# MDrive.net
KiCad netlist of a schematic drawn in Altium Designer
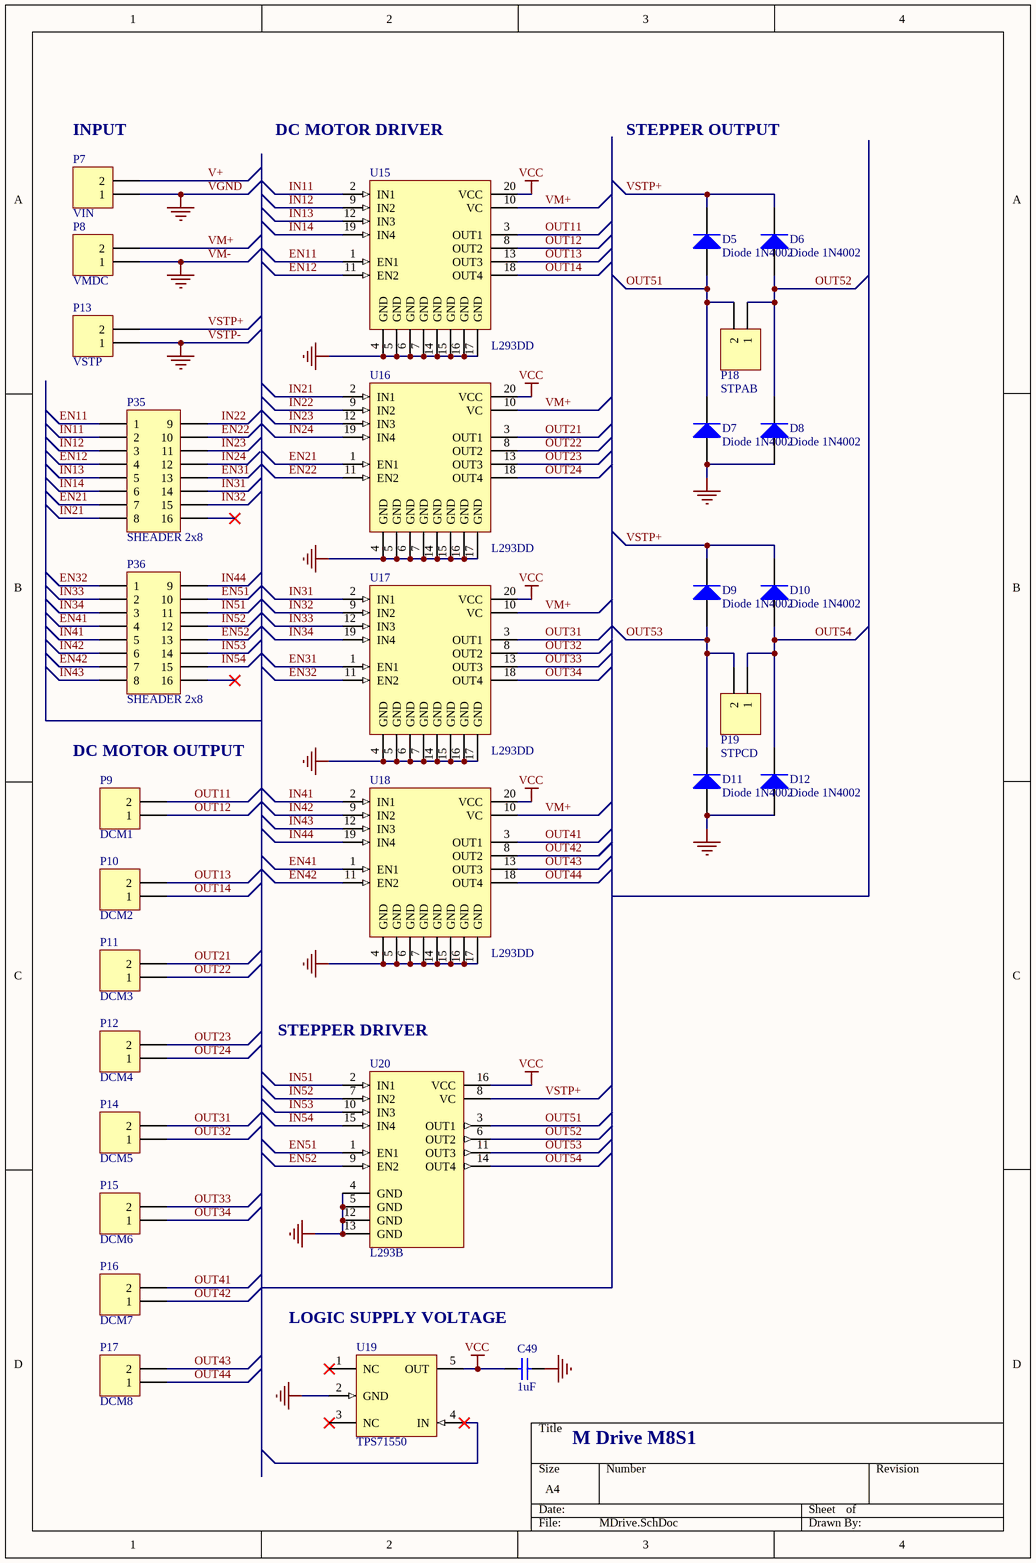
[diagram p0: MDrive.SchDoc]

(export (version "E")
  (design (tool "Eeschema 10.0.6"))
  (components
    (comp (ref "C49")
      (value "1uF")
      (footprint "CAPC2012M")
      (description "Capacitor (Semiconductor SIM Model)")
      (fields (field (name "Comment") "Cap Semi") (field (name "PUBLISHER") "Altium Limited"))
      (libsource (lib "Miscellaneous Devices") (part "Cap Semi"))
    )
    (comp (ref "D5")
      (value "Diode 1N4002")
      (footprint "DO-41")
      (description "1 Amp General Purpose Rectifier")
      (fields (field (name "PUBLISHER") "Altium Limited"))
      (libsource (lib "Miscellaneous Devices") (part "Diode 1N4002"))
    )
    (comp (ref "D6")
      (value "Diode 1N4002")
      (footprint "DO-41")
      (description "1 Amp General Purpose Rectifier")
      (fields (field (name "PUBLISHER") "Altium Limited"))
      (libsource (lib "Miscellaneous Devices") (part "Diode 1N4002"))
    )
    (comp (ref "D7")
      (value "Diode 1N4002")
      (footprint "DO-41")
      (description "1 Amp General Purpose Rectifier")
      (fields (field (name "PUBLISHER") "Altium Limited"))
      (libsource (lib "Miscellaneous Devices") (part "Diode 1N4002"))
    )
    (comp (ref "D8")
      (value "Diode 1N4002")
      (footprint "DO-41")
      (description "1 Amp General Purpose Rectifier")
      (fields (field (name "PUBLISHER") "Altium Limited"))
      (libsource (lib "Miscellaneous Devices") (part "Diode 1N4002"))
    )
    (comp (ref "D9")
      (value "Diode 1N4002")
      (footprint "DO-41")
      (description "1 Amp General Purpose Rectifier")
      (fields (field (name "PUBLISHER") "Altium Limited"))
      (libsource (lib "Miscellaneous Devices") (part "Diode 1N4002"))
    )
    (comp (ref "D10")
      (value "Diode 1N4002")
      (footprint "DO-41")
      (description "1 Amp General Purpose Rectifier")
      (fields (field (name "PUBLISHER") "Altium Limited"))
      (libsource (lib "Miscellaneous Devices") (part "Diode 1N4002"))
    )
    (comp (ref "D11")
      (value "Diode 1N4002")
      (footprint "DO-41")
      (description "1 Amp General Purpose Rectifier")
      (fields (field (name "PUBLISHER") "Altium Limited"))
      (libsource (lib "Miscellaneous Devices") (part "Diode 1N4002"))
    )
    (comp (ref "D12")
      (value "Diode 1N4002")
      (footprint "DO-41")
      (description "1 Amp General Purpose Rectifier")
      (fields (field (name "PUBLISHER") "Altium Limited"))
      (libsource (lib "Miscellaneous Devices") (part "Diode 1N4002"))
    )
    (comp (ref "P7")
      (value "VIN")
      (footprint "AZUL5-2")
      (description "Header, 2-Pin")
      (fields (field (name "PUBLISHER") "Altium Limited"))
      (libsource (lib "Miscellaneous Connectors") (part "Header 2"))
    )
    (comp (ref "P8")
      (value "VMDC")
      (footprint "AZUL5-2")
      (description "Header, 2-Pin")
      (fields (field (name "PUBLISHER") "Altium Limited"))
      (libsource (lib "Miscellaneous Connectors") (part "Header 2"))
    )
    (comp (ref "P9")
      (value "DCM1")
      (footprint "AZUL5-2")
      (description "Header, 2-Pin")
      (fields (field (name "PUBLISHER") "Altium Limited"))
      (libsource (lib "Miscellaneous Connectors") (part "Header 2"))
    )
    (comp (ref "P10")
      (value "DCM2")
      (footprint "AZUL5-2")
      (description "Header, 2-Pin")
      (fields (field (name "PUBLISHER") "Altium Limited"))
      (libsource (lib "Miscellaneous Connectors") (part "Header 2"))
    )
    (comp (ref "P11")
      (value "DCM3")
      (footprint "AZUL5-2")
      (description "Header, 2-Pin")
      (fields (field (name "PUBLISHER") "Altium Limited"))
      (libsource (lib "Miscellaneous Connectors") (part "Header 2"))
    )
    (comp (ref "P12")
      (value "DCM4")
      (footprint "AZUL5-2")
      (description "Header, 2-Pin")
      (fields (field (name "PUBLISHER") "Altium Limited"))
      (libsource (lib "Miscellaneous Connectors") (part "Header 2"))
    )
    (comp (ref "P13")
      (value "VSTP")
      (footprint "AZUL5-2")
      (description "Header, 2-Pin")
      (fields (field (name "PUBLISHER") "Altium Limited"))
      (libsource (lib "Miscellaneous Connectors") (part "Header 2"))
    )
    (comp (ref "P14")
      (value "DCM5")
      (footprint "AZUL5-2")
      (description "Header, 2-Pin")
      (fields (field (name "PUBLISHER") "Altium Limited"))
      (libsource (lib "Miscellaneous Connectors") (part "Header 2"))
    )
    (comp (ref "P15")
      (value "DCM6")
      (footprint "AZUL5-2")
      (description "Header, 2-Pin")
      (fields (field (name "PUBLISHER") "Altium Limited"))
      (libsource (lib "Miscellaneous Connectors") (part "Header 2"))
    )
    (comp (ref "P16")
      (value "DCM7")
      (footprint "AZUL5-2")
      (description "Header, 2-Pin")
      (fields (field (name "PUBLISHER") "Altium Limited"))
      (libsource (lib "Miscellaneous Connectors") (part "Header 2"))
    )
    (comp (ref "P17")
      (value "DCM8")
      (footprint "AZUL5-2")
      (description "Header, 2-Pin")
      (fields (field (name "PUBLISHER") "Altium Limited"))
      (libsource (lib "Miscellaneous Connectors") (part "Header 2"))
    )
    (comp (ref "P18")
      (value "STPAB")
      (footprint "AZUL5-2")
      (description "Header, 2-Pin")
      (fields (field (name "PUBLISHER") "Altium Limited"))
      (libsource (lib "") (part "Header 2_1"))
    )
    (comp (ref "P19")
      (value "STPCD")
      (footprint "AZUL5-2")
      (description "Header, 2-Pin")
      (fields (field (name "PUBLISHER") "Altium Limited"))
      (libsource (lib "") (part "Header 2_1"))
    )
    (comp (ref "P35")
      (value "SHEADER 2x8")
      (footprint "SHBH 2X8")
      (description "Shrouded Box Header: 2x8-Pin, 0.100\" (2.54 mm) Male")
      (libsource (lib "LitoLibrary") (part "SB Header 2x8"))
    )
    (comp (ref "P36")
      (value "SHEADER 2x8")
      (footprint "SHBH 2X8")
      (description "Shrouded Box Header: 2x8-Pin, 0.100\" (2.54 mm) Male")
      (libsource (lib "LitoLibrary") (part "SB Header 2x8"))
    )
    (comp (ref "U15")
      (value "L293DD")
      (footprint "SO20_N")
      (description "Push-Pull Four Channel Driver With Diode")
      (fields (field (name "PUBLISHER") "Altium Limited"))
      (libsource (lib "ST Interface DC & Stepper Motor Controller") (part "L293DD"))
    )
    (comp (ref "U16")
      (value "L293DD")
      (footprint "SO20_N")
      (description "Push-Pull Four Channel Driver With Diode")
      (fields (field (name "PUBLISHER") "Altium Limited"))
      (libsource (lib "ST Interface DC & Stepper Motor Controller") (part "L293DD"))
    )
    (comp (ref "U17")
      (value "L293DD")
      (footprint "SO20_N")
      (description "Push-Pull Four Channel Driver With Diode")
      (fields (field (name "PUBLISHER") "Altium Limited"))
      (libsource (lib "ST Interface DC & Stepper Motor Controller") (part "L293DD"))
    )
    (comp (ref "U18")
      (value "L293DD")
      (footprint "SO20_N")
      (description "Push-Pull Four Channel Driver With Diode")
      (fields (field (name "PUBLISHER") "Altium Limited"))
      (libsource (lib "ST Interface DC & Stepper Motor Controller") (part "L293DD"))
    )
    (comp (ref "U19")
      (value "TPS71550")
      (footprint "SOT353-5L")
      (libsource (lib "LitoLibrary") (part "TPS71550"))
    )
    (comp (ref "U20")
      (value "L293B")
      (footprint "DIP16")
      (description "Push-Pull Four Channel Drivers")
      (fields (field (name "PUBLISHER") "Altium Limited"))
      (libsource (lib "ST Interface DC & Stepper Motor Controller") (part "L293B"))
    )
  )
  (nets
    (net (code "1") (name "/EN11") (class "Default")
      (node (ref "P35") (pin "1") (pinfunction "1_1") (pintype "passive"))
      (node (ref "U15") (pin "1") (pinfunction "EN1_1") (pintype "input"))
    )
    (net (code "2") (name "/EN12") (class "Default")
      (node (ref "P35") (pin "4") (pinfunction "4_4") (pintype "passive"))
      (node (ref "U15") (pin "11") (pinfunction "EN2_11") (pintype "input"))
    )
    (net (code "3") (name "/EN21") (class "Default")
      (node (ref "P35") (pin "7") (pinfunction "7_7") (pintype "passive"))
      (node (ref "U16") (pin "1") (pinfunction "EN1_1") (pintype "input"))
    )
    (net (code "4") (name "/EN22") (class "Default")
      (node (ref "P35") (pin "10") (pinfunction "10_10") (pintype "passive"))
      (node (ref "U16") (pin "11") (pinfunction "EN2_11") (pintype "input"))
    )
    (net (code "5") (name "/EN31") (class "Default")
      (node (ref "P35") (pin "13") (pinfunction "13_13") (pintype "passive"))
      (node (ref "U17") (pin "1") (pinfunction "EN1_1") (pintype "input"))
    )
    (net (code "6") (name "/EN32") (class "Default")
      (node (ref "P36") (pin "1") (pinfunction "1_1") (pintype "passive"))
      (node (ref "U17") (pin "11") (pinfunction "EN2_11") (pintype "input"))
    )
    (net (code "7") (name "/EN41") (class "Default")
      (node (ref "P36") (pin "4") (pinfunction "4_4") (pintype "passive"))
      (node (ref "U18") (pin "1") (pinfunction "EN1_1") (pintype "input"))
    )
    (net (code "8") (name "/EN42") (class "Default")
      (node (ref "P36") (pin "7") (pinfunction "7_7") (pintype "passive"))
      (node (ref "U18") (pin "11") (pinfunction "EN2_11") (pintype "input"))
    )
    (net (code "9") (name "/EN51") (class "Default")
      (node (ref "P36") (pin "10") (pinfunction "10_10") (pintype "passive"))
      (node (ref "U20") (pin "1") (pinfunction "EN1_1") (pintype "input"))
    )
    (net (code "10") (name "/EN52") (class "Default")
      (node (ref "P36") (pin "13") (pinfunction "13_13") (pintype "passive"))
      (node (ref "U20") (pin "9") (pinfunction "EN2_9") (pintype "input"))
    )
    (net (code "11") (name "/IN11") (class "Default")
      (node (ref "P35") (pin "2") (pinfunction "2_2") (pintype "passive"))
      (node (ref "U15") (pin "2") (pinfunction "IN1_2") (pintype "input"))
    )
    (net (code "12") (name "/IN12") (class "Default")
      (node (ref "P35") (pin "3") (pinfunction "3_3") (pintype "passive"))
      (node (ref "U15") (pin "9") (pinfunction "IN2_9") (pintype "input"))
    )
    (net (code "13") (name "/IN13") (class "Default")
      (node (ref "P35") (pin "5") (pinfunction "5_5") (pintype "passive"))
      (node (ref "U15") (pin "12") (pinfunction "IN3_12") (pintype "input"))
    )
    (net (code "14") (name "/IN14") (class "Default")
      (node (ref "P35") (pin "6") (pinfunction "6_6") (pintype "passive"))
      (node (ref "U15") (pin "19") (pinfunction "IN4_19") (pintype "input"))
    )
    (net (code "15") (name "/IN21") (class "Default")
      (node (ref "P35") (pin "8") (pinfunction "8_8") (pintype "passive"))
      (node (ref "U16") (pin "2") (pinfunction "IN1_2") (pintype "input"))
    )
    (net (code "16") (name "/IN22") (class "Default")
      (node (ref "P35") (pin "9") (pinfunction "9_9") (pintype "passive"))
      (node (ref "U16") (pin "9") (pinfunction "IN2_9") (pintype "input"))
    )
    (net (code "17") (name "/IN23") (class "Default")
      (node (ref "P35") (pin "11") (pinfunction "11_11") (pintype "passive"))
      (node (ref "U16") (pin "12") (pinfunction "IN3_12") (pintype "input"))
    )
    (net (code "18") (name "/IN24") (class "Default")
      (node (ref "P35") (pin "12") (pinfunction "12_12") (pintype "passive"))
      (node (ref "U16") (pin "19") (pinfunction "IN4_19") (pintype "input"))
    )
    (net (code "19") (name "/IN31") (class "Default")
      (node (ref "P35") (pin "14") (pinfunction "14_14") (pintype "passive"))
      (node (ref "U17") (pin "2") (pinfunction "IN1_2") (pintype "input"))
    )
    (net (code "20") (name "/IN32") (class "Default")
      (node (ref "P35") (pin "15") (pinfunction "15_15") (pintype "passive"))
      (node (ref "U17") (pin "9") (pinfunction "IN2_9") (pintype "input"))
    )
    (net (code "21") (name "/IN33") (class "Default")
      (node (ref "P36") (pin "2") (pinfunction "2_2") (pintype "passive"))
      (node (ref "U17") (pin "12") (pinfunction "IN3_12") (pintype "input"))
    )
    (net (code "22") (name "/IN34") (class "Default")
      (node (ref "P36") (pin "3") (pinfunction "3_3") (pintype "passive"))
      (node (ref "U17") (pin "19") (pinfunction "IN4_19") (pintype "input"))
    )
    (net (code "23") (name "/IN41") (class "Default")
      (node (ref "P36") (pin "5") (pinfunction "5_5") (pintype "passive"))
      (node (ref "U18") (pin "2") (pinfunction "IN1_2") (pintype "input"))
    )
    (net (code "24") (name "/IN42") (class "Default")
      (node (ref "P36") (pin "6") (pinfunction "6_6") (pintype "passive"))
      (node (ref "U18") (pin "9") (pinfunction "IN2_9") (pintype "input"))
    )
    (net (code "25") (name "/IN43") (class "Default")
      (node (ref "P36") (pin "8") (pinfunction "8_8") (pintype "passive"))
      (node (ref "U18") (pin "12") (pinfunction "IN3_12") (pintype "input"))
    )
    (net (code "26") (name "/IN44") (class "Default")
      (node (ref "P36") (pin "9") (pinfunction "9_9") (pintype "passive"))
      (node (ref "U18") (pin "19") (pinfunction "IN4_19") (pintype "input"))
    )
    (net (code "27") (name "/IN51") (class "Default")
      (node (ref "P36") (pin "11") (pinfunction "11_11") (pintype "passive"))
      (node (ref "U20") (pin "2") (pinfunction "IN1_2") (pintype "input"))
    )
    (net (code "28") (name "/IN52") (class "Default")
      (node (ref "P36") (pin "12") (pinfunction "12_12") (pintype "passive"))
      (node (ref "U20") (pin "7") (pinfunction "IN2_7") (pintype "input"))
    )
    (net (code "29") (name "/IN53") (class "Default")
      (node (ref "P36") (pin "14") (pinfunction "14_14") (pintype "passive"))
      (node (ref "U20") (pin "10") (pinfunction "IN3_10") (pintype "input"))
    )
    (net (code "30") (name "/IN54") (class "Default")
      (node (ref "P36") (pin "15") (pinfunction "15_15") (pintype "passive"))
      (node (ref "U20") (pin "15") (pinfunction "IN4_15") (pintype "input"))
    )
    (net (code "31") (name "/OUT11") (class "Default")
      (node (ref "P9") (pin "2") (pinfunction "2_2") (pintype "passive"))
      (node (ref "U15") (pin "3") (pinfunction "OUT1_3") (pintype "tri_state"))
    )
    (net (code "32") (name "/OUT12") (class "Default")
      (node (ref "P9") (pin "1") (pinfunction "1_1") (pintype "passive"))
      (node (ref "U15") (pin "8") (pinfunction "OUT2_8") (pintype "tri_state"))
    )
    (net (code "33") (name "/OUT13") (class "Default")
      (node (ref "P10") (pin "2") (pinfunction "2_2") (pintype "passive"))
      (node (ref "U15") (pin "13") (pinfunction "OUT3_13") (pintype "tri_state"))
    )
    (net (code "34") (name "/OUT14") (class "Default")
      (node (ref "P10") (pin "1") (pinfunction "1_1") (pintype "passive"))
      (node (ref "U15") (pin "18") (pinfunction "OUT4_18") (pintype "tri_state"))
    )
    (net (code "35") (name "/OUT21") (class "Default")
      (node (ref "P11") (pin "2") (pinfunction "2_2") (pintype "passive"))
      (node (ref "U16") (pin "3") (pinfunction "OUT1_3") (pintype "tri_state"))
    )
    (net (code "36") (name "/OUT22") (class "Default")
      (node (ref "P11") (pin "1") (pinfunction "1_1") (pintype "passive"))
      (node (ref "U16") (pin "8") (pinfunction "OUT2_8") (pintype "tri_state"))
    )
    (net (code "37") (name "/OUT23") (class "Default")
      (node (ref "P12") (pin "2") (pinfunction "2_2") (pintype "passive"))
      (node (ref "U16") (pin "13") (pinfunction "OUT3_13") (pintype "tri_state"))
    )
    (net (code "38") (name "/OUT24") (class "Default")
      (node (ref "P12") (pin "1") (pinfunction "1_1") (pintype "passive"))
      (node (ref "U16") (pin "18") (pinfunction "OUT4_18") (pintype "tri_state"))
    )
    (net (code "39") (name "/OUT31") (class "Default")
      (node (ref "P14") (pin "2") (pinfunction "2_2") (pintype "passive"))
      (node (ref "U17") (pin "3") (pinfunction "OUT1_3") (pintype "tri_state"))
    )
    (net (code "40") (name "/OUT32") (class "Default")
      (node (ref "P14") (pin "1") (pinfunction "1_1") (pintype "passive"))
      (node (ref "U17") (pin "8") (pinfunction "OUT2_8") (pintype "tri_state"))
    )
    (net (code "41") (name "/OUT33") (class "Default")
      (node (ref "P15") (pin "2") (pinfunction "2_2") (pintype "passive"))
      (node (ref "U17") (pin "13") (pinfunction "OUT3_13") (pintype "tri_state"))
    )
    (net (code "42") (name "/OUT34") (class "Default")
      (node (ref "P15") (pin "1") (pinfunction "1_1") (pintype "passive"))
      (node (ref "U17") (pin "18") (pinfunction "OUT4_18") (pintype "tri_state"))
    )
    (net (code "43") (name "/OUT41") (class "Default")
      (node (ref "P16") (pin "2") (pinfunction "2_2") (pintype "passive"))
      (node (ref "U18") (pin "3") (pinfunction "OUT1_3") (pintype "tri_state"))
    )
    (net (code "44") (name "/OUT42") (class "Default")
      (node (ref "P16") (pin "1") (pinfunction "1_1") (pintype "passive"))
      (node (ref "U18") (pin "8") (pinfunction "OUT2_8") (pintype "tri_state"))
    )
    (net (code "45") (name "/OUT43") (class "Default")
      (node (ref "P17") (pin "2") (pinfunction "2_2") (pintype "passive"))
      (node (ref "U18") (pin "13") (pinfunction "OUT3_13") (pintype "tri_state"))
    )
    (net (code "46") (name "/OUT44") (class "Default")
      (node (ref "P17") (pin "1") (pinfunction "1_1") (pintype "passive"))
      (node (ref "U18") (pin "18") (pinfunction "OUT4_18") (pintype "tri_state"))
    )
    (net (code "47") (name "/OUT51") (class "Default")
      (node (ref "D5") (pin "1") (pinfunction "A_1") (pintype "passive"))
      (node (ref "D7") (pin "2") (pinfunction "K_2") (pintype "passive"))
      (node (ref "P18") (pin "2") (pinfunction "2_2") (pintype "passive"))
      (node (ref "U20") (pin "3") (pinfunction "OUT1_3") (pintype "output"))
    )
    (net (code "48") (name "/OUT52") (class "Default")
      (node (ref "D6") (pin "1") (pinfunction "A_1") (pintype "passive"))
      (node (ref "D8") (pin "2") (pinfunction "K_2") (pintype "passive"))
      (node (ref "P18") (pin "1") (pinfunction "1_1") (pintype "passive"))
      (node (ref "U20") (pin "6") (pinfunction "OUT2_6") (pintype "output"))
    )
    (net (code "49") (name "/OUT53") (class "Default")
      (node (ref "D11") (pin "2") (pinfunction "K_2") (pintype "passive"))
      (node (ref "D9") (pin "1") (pinfunction "A_1") (pintype "passive"))
      (node (ref "P19") (pin "2") (pinfunction "2_2") (pintype "passive"))
      (node (ref "U20") (pin "11") (pinfunction "OUT3_11") (pintype "output"))
    )
    (net (code "50") (name "/OUT54") (class "Default")
      (node (ref "D10") (pin "1") (pinfunction "A_1") (pintype "passive"))
      (node (ref "D12") (pin "2") (pinfunction "K_2") (pintype "passive"))
      (node (ref "P19") (pin "1") (pinfunction "1_1") (pintype "passive"))
      (node (ref "U20") (pin "14") (pinfunction "OUT4_14") (pintype "output"))
    )
    (net (code "51") (name "/V+") (class "Default")
      (node (ref "P7") (pin "2") (pinfunction "2_2") (pintype "passive"))
    )
    (net (code "52") (name "/VM+") (class "Default")
      (node (ref "P8") (pin "2") (pinfunction "2_2") (pintype "passive"))
      (node (ref "U15") (pin "10") (pinfunction "VC_10") (pintype "power_in"))
      (node (ref "U16") (pin "10") (pinfunction "VC_10") (pintype "power_in"))
      (node (ref "U17") (pin "10") (pinfunction "VC_10") (pintype "power_in"))
      (node (ref "U18") (pin "10") (pinfunction "VC_10") (pintype "power_in"))
    )
    (net (code "53") (name "/VSTP+") (class "Default")
      (node (ref "D10") (pin "2") (pinfunction "K_2") (pintype "passive"))
      (node (ref "D5") (pin "2") (pinfunction "K_2") (pintype "passive"))
      (node (ref "D6") (pin "2") (pinfunction "K_2") (pintype "passive"))
      (node (ref "D9") (pin "2") (pinfunction "K_2") (pintype "passive"))
      (node (ref "P13") (pin "2") (pinfunction "2_2") (pintype "passive"))
      (node (ref "U20") (pin "8") (pinfunction "VC_8") (pintype "power_in"))
    )
    (net (code "54") (name "GND") (class "Default")
      (node (ref "C49") (pin "2") (pinfunction "2_2") (pintype "passive"))
      (node (ref "D11") (pin "1") (pinfunction "A_1") (pintype "passive"))
      (node (ref "D12") (pin "1") (pinfunction "A_1") (pintype "passive"))
      (node (ref "D7") (pin "1") (pinfunction "A_1") (pintype "passive"))
      (node (ref "D8") (pin "1") (pinfunction "A_1") (pintype "passive"))
      (node (ref "P13") (pin "1") (pinfunction "1_1") (pintype "passive"))
      (node (ref "P7") (pin "1") (pinfunction "1_1") (pintype "passive"))
      (node (ref "P8") (pin "1") (pinfunction "1_1") (pintype "passive"))
      (node (ref "U15") (pin "14") (pinfunction "GND_14") (pintype "power_in"))
      (node (ref "U15") (pin "15") (pinfunction "GND_15") (pintype "power_in"))
      (node (ref "U15") (pin "16") (pinfunction "GND_16") (pintype "power_in"))
      (node (ref "U15") (pin "17") (pinfunction "GND_17") (pintype "power_in"))
      (node (ref "U15") (pin "4") (pinfunction "GND_4") (pintype "power_in"))
      (node (ref "U15") (pin "5") (pinfunction "GND_5") (pintype "power_in"))
      (node (ref "U15") (pin "6") (pinfunction "GND_6") (pintype "power_in"))
      (node (ref "U15") (pin "7") (pinfunction "GND_7") (pintype "power_in"))
      (node (ref "U16") (pin "14") (pinfunction "GND_14") (pintype "power_in"))
      (node (ref "U16") (pin "15") (pinfunction "GND_15") (pintype "power_in"))
      (node (ref "U16") (pin "16") (pinfunction "GND_16") (pintype "power_in"))
      (node (ref "U16") (pin "17") (pinfunction "GND_17") (pintype "power_in"))
      (node (ref "U16") (pin "4") (pinfunction "GND_4") (pintype "power_in"))
      (node (ref "U16") (pin "5") (pinfunction "GND_5") (pintype "power_in"))
      (node (ref "U16") (pin "6") (pinfunction "GND_6") (pintype "power_in"))
      (node (ref "U16") (pin "7") (pinfunction "GND_7") (pintype "power_in"))
      (node (ref "U17") (pin "14") (pinfunction "GND_14") (pintype "power_in"))
      (node (ref "U17") (pin "15") (pinfunction "GND_15") (pintype "power_in"))
      (node (ref "U17") (pin "16") (pinfunction "GND_16") (pintype "power_in"))
      (node (ref "U17") (pin "17") (pinfunction "GND_17") (pintype "power_in"))
      (node (ref "U17") (pin "4") (pinfunction "GND_4") (pintype "power_in"))
      (node (ref "U17") (pin "5") (pinfunction "GND_5") (pintype "power_in"))
      (node (ref "U17") (pin "6") (pinfunction "GND_6") (pintype "power_in"))
      (node (ref "U17") (pin "7") (pinfunction "GND_7") (pintype "power_in"))
      (node (ref "U18") (pin "14") (pinfunction "GND_14") (pintype "power_in"))
      (node (ref "U18") (pin "15") (pinfunction "GND_15") (pintype "power_in"))
      (node (ref "U18") (pin "16") (pinfunction "GND_16") (pintype "power_in"))
      (node (ref "U18") (pin "17") (pinfunction "GND_17") (pintype "power_in"))
      (node (ref "U18") (pin "4") (pinfunction "GND_4") (pintype "power_in"))
      (node (ref "U18") (pin "5") (pinfunction "GND_5") (pintype "power_in"))
      (node (ref "U18") (pin "6") (pinfunction "GND_6") (pintype "power_in"))
      (node (ref "U18") (pin "7") (pinfunction "GND_7") (pintype "power_in"))
      (node (ref "U19") (pin "2") (pinfunction "GND_2") (pintype "input"))
      (node (ref "U20") (pin "12") (pinfunction "GND_12") (pintype "power_in"))
      (node (ref "U20") (pin "13") (pinfunction "GND_13") (pintype "power_in"))
      (node (ref "U20") (pin "4") (pinfunction "GND_4") (pintype "power_in"))
      (node (ref "U20") (pin "5") (pinfunction "GND_5") (pintype "power_in"))
    )
    (net (code "55") (name "VCC") (class "Default")
      (node (ref "C49") (pin "1") (pinfunction "1_1") (pintype "passive"))
      (node (ref "U15") (pin "20") (pinfunction "VCC_20") (pintype "power_in"))
      (node (ref "U16") (pin "20") (pinfunction "VCC_20") (pintype "power_in"))
      (node (ref "U17") (pin "20") (pinfunction "VCC_20") (pintype "power_in"))
      (node (ref "U18") (pin "20") (pinfunction "VCC_20") (pintype "power_in"))
      (node (ref "U19") (pin "5") (pinfunction "OUT_5") (pintype "passive"))
      (node (ref "U20") (pin "16") (pinfunction "VCC_16") (pintype "power_in"))
    )
    (net (code "56") (name "unconnected-(P35-Pad16)") (class "Default")
      (node (ref "P35") (pin "16") (pinfunction "16_16") (pintype "passive+no_connect"))
    )
    (net (code "57") (name "unconnected-(P36-Pad16)") (class "Default")
      (node (ref "P36") (pin "16") (pinfunction "16_16") (pintype "passive+no_connect"))
    )
    (net (code "58") (name "unconnected-(U19-IN-Pad4)") (class "Default")
      (node (ref "U19") (pin "4") (pinfunction "IN_4") (pintype "input+no_connect"))
    )
    (net (code "59") (name "unconnected-(U19-NC-Pad1)") (class "Default")
      (node (ref "U19") (pin "1") (pinfunction "NC_1") (pintype "passive+no_connect"))
    )
    (net (code "60") (name "unconnected-(U19-NC-Pad3)") (class "Default")
      (node (ref "U19") (pin "3") (pinfunction "NC_3") (pintype "passive+no_connect"))
    )
  )
)
